# SFPGA.net
KiCad netlist of a schematic drawn in Altium Designer
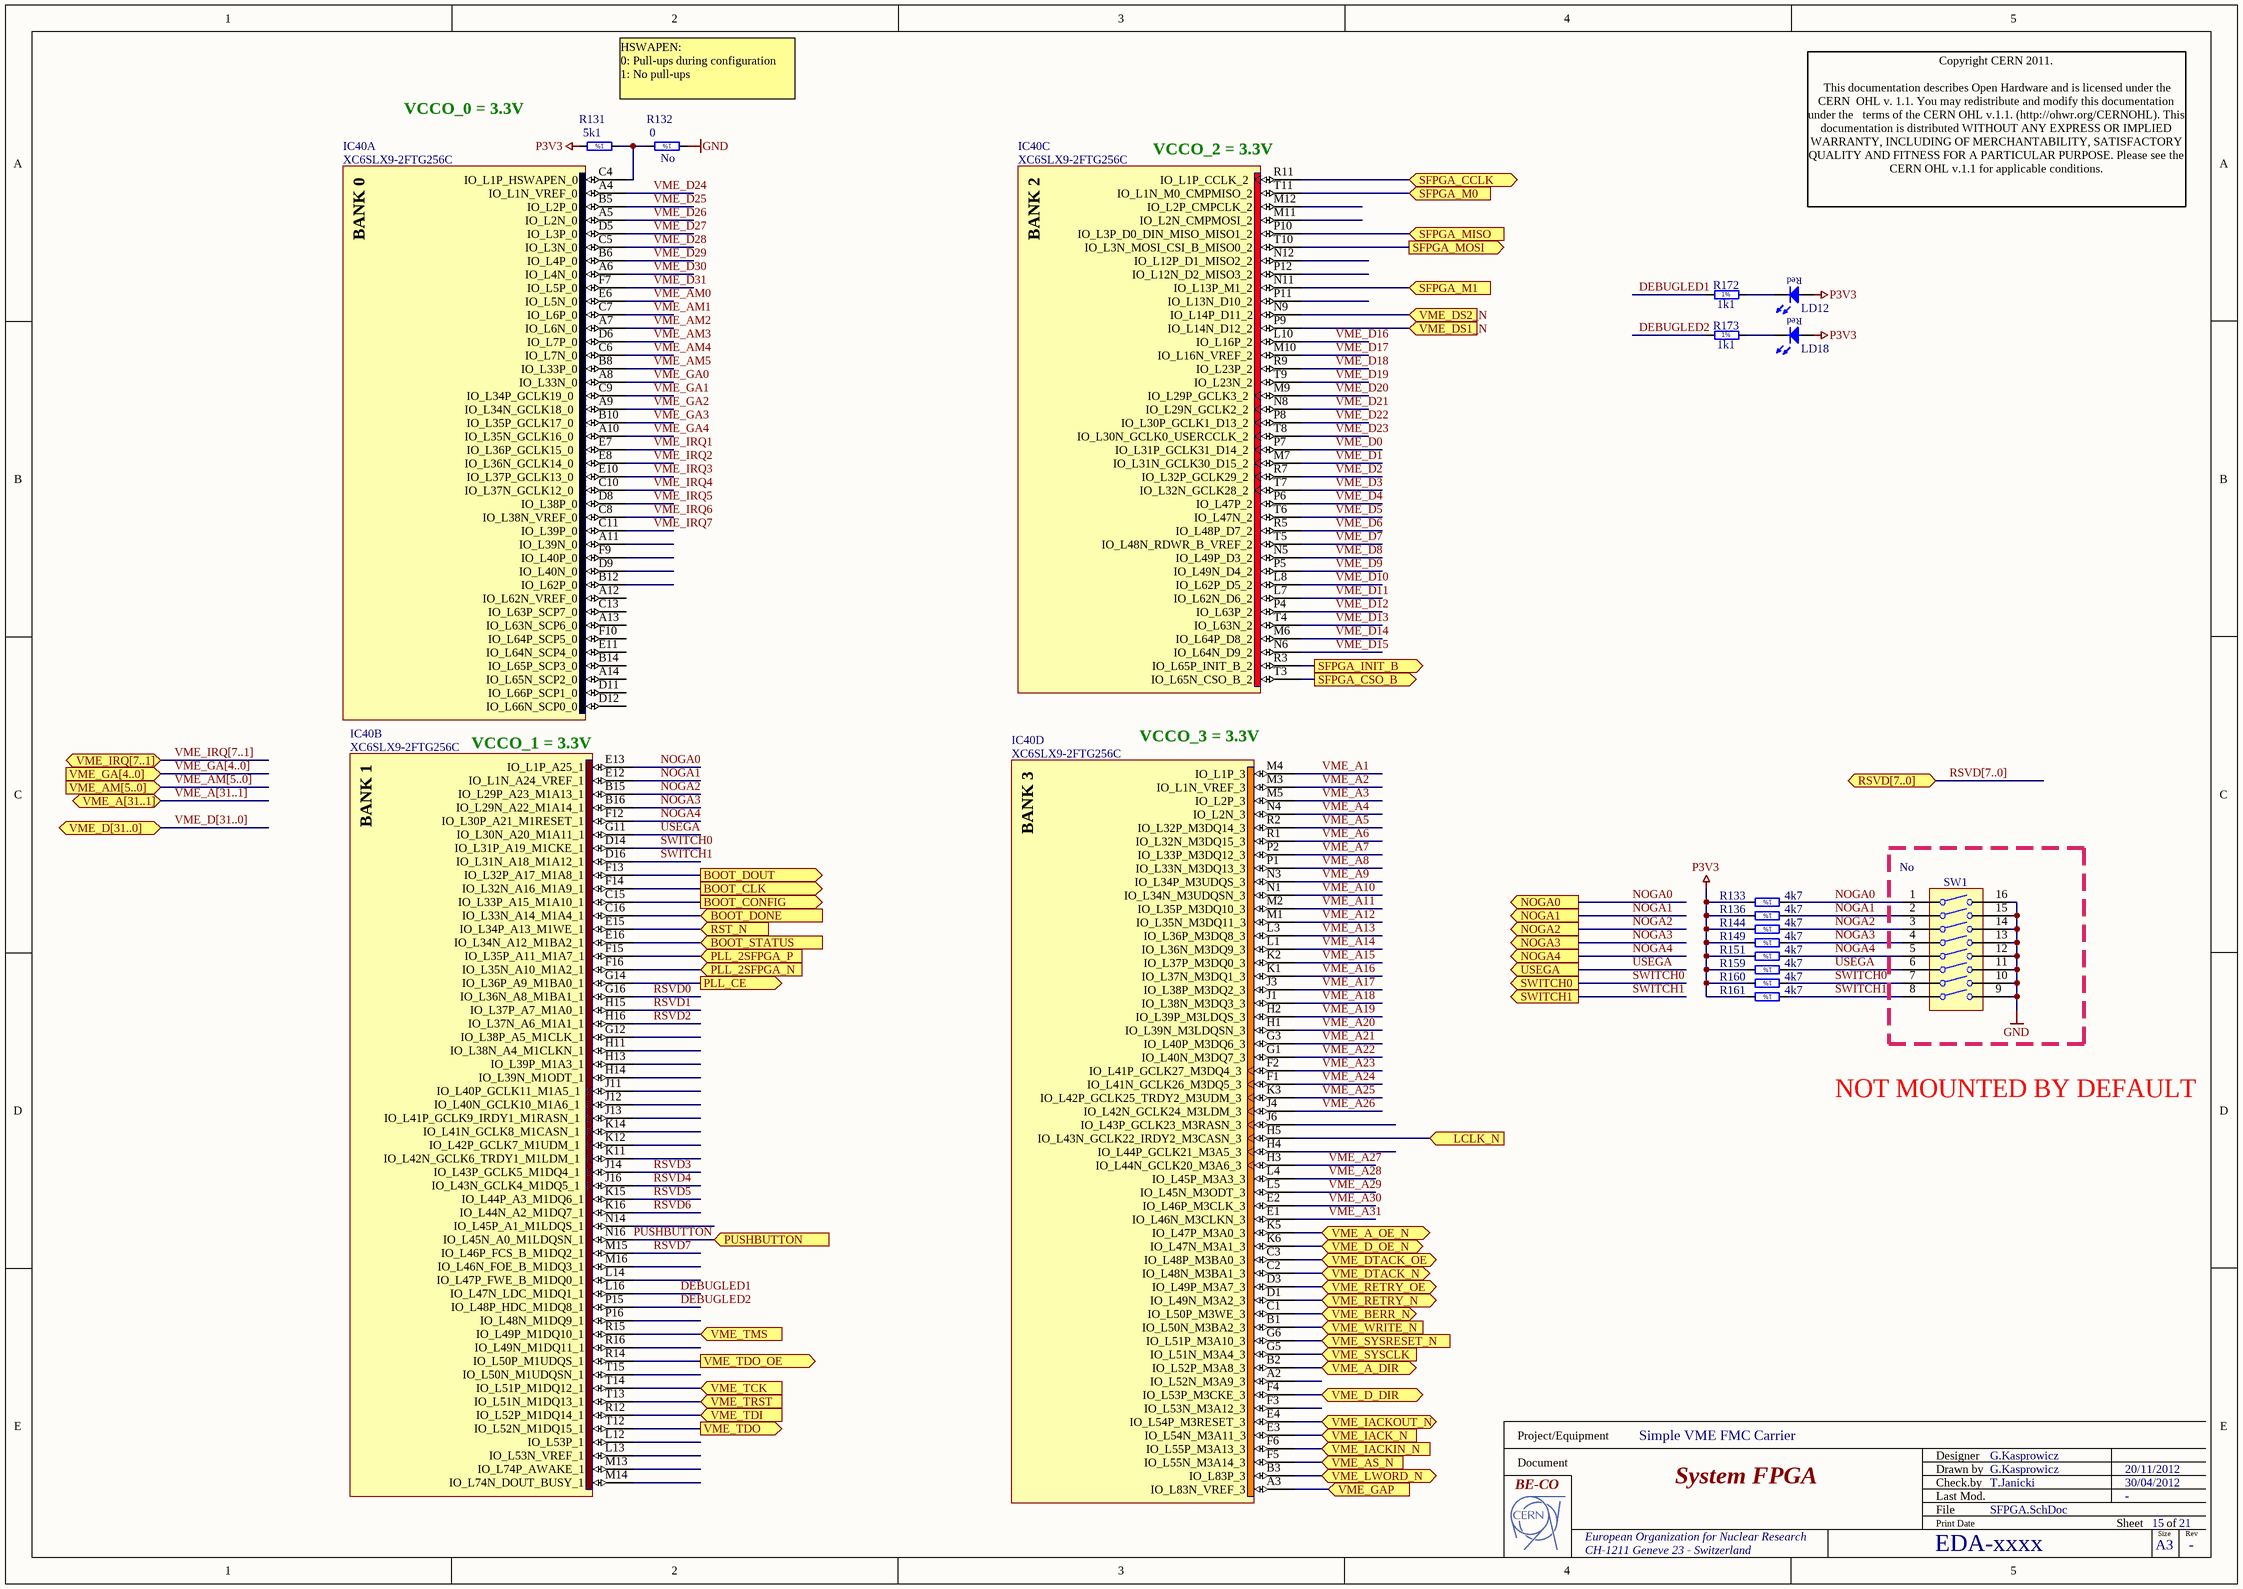
[diagram p0: SFPGA.SchDoc]

(export (version "E")
  (design (tool "Eeschema 10.0.6"))
  (components
    (comp (ref "IC40")
      (value "XC6SLX9-2FTG256C")
      (footprint "BGA256C100P16X16_1700X1700X155")
      (fields (field (name "MANUFACTURER") "XILINX") (field (name "AUTHOR") "CERN DEM JLC"))
      (libsource (lib "ICs And Semiconductors") (part "XC6SLX9-2FTG256C"))
    )
    (comp (ref "LD12")
      (value "Red")
      (footprint "LEDC1608X80N_RED")
      (description "LED Red 1C 2A")
      (fields
        (field (name "PART NUMBER") "LED_ROHM_SML-311UTT86K")
        (field (name "MANUFACTURER") "ROHM")
        (field (name "AUTHOR") "CERN DEM JLC")
      )
      (libsource (lib "ICs And Semiconductors") (part "LED Red 1C 2A"))
    )
    (comp (ref "LD18")
      (value "Red")
      (footprint "LEDC1608X80N_RED")
      (description "LED Red 1C 2A")
      (fields
        (field (name "PART NUMBER") "LED_ROHM_SML-311UTT86K")
        (field (name "MANUFACTURER") "ROHM")
        (field (name "AUTHOR") "CERN DEM JLC")
      )
      (libsource (lib "ICs And Semiconductors") (part "LED Red 1C 2A"))
    )
    (comp (ref "R131")
      (value "5k1")
      (footprint "RESC1608X55N")
      (description "Resistor - 1%")
      (fields
        (field (name "PART NUMBER") "R0603_5K1_1%_0.1W_100PPM")
        (field (name "POWER") "0.1W")
        (field (name "AUTHOR") "CERN DEM JLC")
      )
      (libsource (lib "Resistors") (part "Resistor - 1%"))
    )
    (comp (ref "R132")
      (value "0")
      (footprint "RESC1608X55N")
      (description "Resistor - 1%")
      (fields
        (field (name "PART NUMBER") "R0603_0R_JUMPER")
        (field (name "MANUFACTURER") "GENERIC")
        (field (name "MOUNTED") "No")
        (field (name "AUTHOR") "CERN DEM JLC")
      )
      (libsource (lib "Resistors") (part "Resistor - 1%"))
    )
    (comp (ref "R133")
      (value "4k7")
      (footprint "RESC1608X55N")
      (description "Resistor - 1%")
      (fields
        (field (name "PART NUMBER") "R0603_4K7_1%_0.1W_100PPM")
        (field (name "POWER") "0.1W")
        (field (name "AUTHOR") "CERN DEM JLC")
      )
      (libsource (lib "Resistors") (part "Resistor - 1%"))
    )
    (comp (ref "R136")
      (value "4k7")
      (footprint "RESC1608X55N")
      (description "Resistor - 1%")
      (fields
        (field (name "PART NUMBER") "R0603_4K7_1%_0.1W_100PPM")
        (field (name "POWER") "0.1W")
        (field (name "AUTHOR") "CERN DEM JLC")
      )
      (libsource (lib "Resistors") (part "Resistor - 1%"))
    )
    (comp (ref "R144")
      (value "4k7")
      (footprint "RESC1608X55N")
      (description "Resistor - 1%")
      (fields
        (field (name "PART NUMBER") "R0603_4K7_1%_0.1W_100PPM")
        (field (name "POWER") "0.1W")
        (field (name "AUTHOR") "CERN DEM JLC")
      )
      (libsource (lib "Resistors") (part "Resistor - 1%"))
    )
    (comp (ref "R149")
      (value "4k7")
      (footprint "RESC1608X55N")
      (description "Resistor - 1%")
      (fields
        (field (name "PART NUMBER") "R0603_4K7_1%_0.1W_100PPM")
        (field (name "POWER") "0.1W")
        (field (name "AUTHOR") "CERN DEM JLC")
      )
      (libsource (lib "Resistors") (part "Resistor - 1%"))
    )
    (comp (ref "R151")
      (value "4k7")
      (footprint "RESC1608X55N")
      (description "Resistor - 1%")
      (fields
        (field (name "PART NUMBER") "R0603_4K7_1%_0.1W_100PPM")
        (field (name "POWER") "0.1W")
        (field (name "AUTHOR") "CERN DEM JLC")
      )
      (libsource (lib "Resistors") (part "Resistor - 1%"))
    )
    (comp (ref "R159")
      (value "4k7")
      (footprint "RESC1608X55N")
      (description "Resistor - 1%")
      (fields
        (field (name "PART NUMBER") "R0603_4K7_1%_0.1W_100PPM")
        (field (name "POWER") "0.1W")
        (field (name "AUTHOR") "CERN DEM JLC")
      )
      (libsource (lib "Resistors") (part "Resistor - 1%"))
    )
    (comp (ref "R160")
      (value "4k7")
      (footprint "RESC1608X55N")
      (description "Resistor - 1%")
      (fields
        (field (name "PART NUMBER") "R0603_4K7_1%_0.1W_100PPM")
        (field (name "POWER") "0.1W")
        (field (name "AUTHOR") "CERN DEM JLC")
      )
      (libsource (lib "Resistors") (part "Resistor - 1%"))
    )
    (comp (ref "R161")
      (value "4k7")
      (footprint "RESC1608X55N")
      (description "Resistor - 1%")
      (fields
        (field (name "PART NUMBER") "R0603_4K7_1%_0.1W_100PPM")
        (field (name "POWER") "0.1W")
        (field (name "AUTHOR") "CERN DEM JLC")
      )
      (libsource (lib "Resistors") (part "Resistor - 1%"))
    )
    (comp (ref "R172")
      (value "1k1")
      (footprint "RESC1608X55N")
      (description "Resistor - 1%")
      (fields
        (field (name "PART NUMBER") "R0603_1K1_1%_0.1W_100PPM")
        (field (name "POWER") "0.1W")
        (field (name "AUTHOR") "CERN DEM JLC")
      )
      (libsource (lib "Resistors") (part "Resistor - 1%"))
    )
    (comp (ref "R173")
      (value "1k1")
      (footprint "RESC1608X55N")
      (description "Resistor - 1%")
      (fields
        (field (name "PART NUMBER") "R0603_1K1_1%_0.1W_100PPM")
        (field (name "POWER") "0.1W")
        (field (name "AUTHOR") "CERN DEM JLC")
      )
      (libsource (lib "Resistors") (part "Resistor - 1%"))
    )
    (comp (ref "SW1")
      (value "Switch")
      (footprint "SW_TYCO_1-1571983-0")
      (description "8 Ways SPST DIP Switch")
      (fields
        (field (name "PART NUMBER") "SW_TYCO_1-1571983-0")
        (field (name "MOUNTED") "No")
        (field (name "MANUFACTURER") "TYCO")
        (field (name "AUTHOR") "CERN DEM JLC")
      )
      (libsource (lib "Eletro-mechanical") (part "SW 8x SPST DIP Switch"))
    )
  )
  (nets
    (net (code "1") (name "/BOOT_CLK") (class "Default")
      (node (ref "IC40") (pin "F14") (pinfunction "IO_L32N_A16_M1A9_1_F14") (pintype "bidirectional"))
    )
    (net (code "2") (name "/BOOT_CONFIG") (class "Default")
      (node (ref "IC40") (pin "C15") (pinfunction "IO_L33P_A15_M1A10_1_C15") (pintype "bidirectional"))
    )
    (net (code "3") (name "/BOOT_DONE") (class "Default")
      (node (ref "IC40") (pin "C16") (pinfunction "IO_L33N_A14_M1A4_1_C16") (pintype "bidirectional"))
    )
    (net (code "4") (name "/BOOT_DOUT") (class "Default")
      (node (ref "IC40") (pin "F13") (pinfunction "IO_L32P_A17_M1A8_1_F13") (pintype "bidirectional"))
    )
    (net (code "5") (name "/BOOT_STATUS") (class "Default")
      (node (ref "IC40") (pin "E16") (pinfunction "IO_L34N_A12_M1BA2_1_E16") (pintype "bidirectional"))
    )
    (net (code "6") (name "/DEBUGLED1") (class "Default")
      (node (ref "IC40") (pin "L16") (pinfunction "IO_L47N_LDC_M1DQ1_1_L16") (pintype "bidirectional"))
      (node (ref "R172") (pin "1") (pinfunction "1_1") (pintype "passive"))
    )
    (net (code "7") (name "/DEBUGLED2") (class "Default")
      (node (ref "IC40") (pin "P15") (pinfunction "IO_L48P_HDC_M1DQ8_1_P15") (pintype "bidirectional"))
      (node (ref "R173") (pin "1") (pinfunction "1_1") (pintype "passive"))
    )
    (net (code "8") (name "/LCLK_N") (class "Default")
      (node (ref "IC40") (pin "H5") (pinfunction "IO_L43N_GCLK22_IRDY2_M3CASN_3_H5") (pintype "bidirectional"))
    )
    (net (code "9") (name "/NOGA0") (class "Default")
      (node (ref "IC40") (pin "E13") (pinfunction "IO_L1P_A25_1_E13") (pintype "bidirectional"))
      (node (ref "R133") (pin "1") (pinfunction "1_1") (pintype "passive"))
      (node (ref "SW1") (pin "1") (pinfunction "1_1") (pintype "passive"))
    )
    (net (code "10") (name "/NOGA1") (class "Default")
      (node (ref "IC40") (pin "E12") (pinfunction "IO_L1N_A24_VREF_1_E12") (pintype "bidirectional"))
      (node (ref "R136") (pin "1") (pinfunction "1_1") (pintype "passive"))
      (node (ref "SW1") (pin "2") (pinfunction "2_2") (pintype "passive"))
    )
    (net (code "11") (name "/NOGA2") (class "Default")
      (node (ref "IC40") (pin "B15") (pinfunction "IO_L29P_A23_M1A13_1_B15") (pintype "bidirectional"))
      (node (ref "R144") (pin "1") (pinfunction "1_1") (pintype "passive"))
      (node (ref "SW1") (pin "3") (pinfunction "3_3") (pintype "passive"))
    )
    (net (code "12") (name "/NOGA3") (class "Default")
      (node (ref "IC40") (pin "B16") (pinfunction "IO_L29N_A22_M1A14_1_B16") (pintype "bidirectional"))
      (node (ref "R149") (pin "1") (pinfunction "1_1") (pintype "passive"))
      (node (ref "SW1") (pin "4") (pinfunction "4_4") (pintype "passive"))
    )
    (net (code "13") (name "/NOGA4") (class "Default")
      (node (ref "IC40") (pin "F12") (pinfunction "IO_L30P_A21_M1RESET_1_F12") (pintype "bidirectional"))
      (node (ref "R151") (pin "1") (pinfunction "1_1") (pintype "passive"))
      (node (ref "SW1") (pin "5") (pinfunction "5_5") (pintype "passive"))
    )
    (net (code "14") (name "/PLL_2SFPGA_N") (class "Default")
      (node (ref "IC40") (pin "F16") (pinfunction "IO_L35N_A10_M1A2_1_F16") (pintype "bidirectional"))
    )
    (net (code "15") (name "/PLL_2SFPGA_P") (class "Default")
      (node (ref "IC40") (pin "F15") (pinfunction "IO_L35P_A11_M1A7_1_F15") (pintype "bidirectional"))
    )
    (net (code "16") (name "/PLL_CE") (class "Default")
      (node (ref "IC40") (pin "G14") (pinfunction "IO_L36P_A9_M1BA0_1_G14") (pintype "bidirectional"))
    )
    (net (code "17") (name "/PUSHBUTTON") (class "Default")
      (node (ref "IC40") (pin "N16") (pinfunction "IO_L45N_A0_M1LDQSN_1_N16") (pintype "bidirectional"))
    )
    (net (code "18") (name "/RST_N") (class "Default")
      (node (ref "IC40") (pin "E15") (pinfunction "IO_L34P_A13_M1WE_1_E15") (pintype "bidirectional"))
    )
    (net (code "19") (name "/RSVD0") (class "Default")
      (node (ref "IC40") (pin "G16") (pinfunction "IO_L36N_A8_M1BA1_1_G16") (pintype "bidirectional"))
    )
    (net (code "20") (name "/RSVD1") (class "Default")
      (node (ref "IC40") (pin "H15") (pinfunction "IO_L37P_A7_M1A0_1_H15") (pintype "bidirectional"))
    )
    (net (code "21") (name "/RSVD2") (class "Default")
      (node (ref "IC40") (pin "H16") (pinfunction "IO_L37N_A6_M1A1_1_H16") (pintype "bidirectional"))
    )
    (net (code "22") (name "/RSVD3") (class "Default")
      (node (ref "IC40") (pin "J14") (pinfunction "IO_L43P_GCLK5_M1DQ4_1_J14") (pintype "bidirectional"))
    )
    (net (code "23") (name "/RSVD4") (class "Default")
      (node (ref "IC40") (pin "J16") (pinfunction "IO_L43N_GCLK4_M1DQ5_1_J16") (pintype "bidirectional"))
    )
    (net (code "24") (name "/RSVD5") (class "Default")
      (node (ref "IC40") (pin "K15") (pinfunction "IO_L44P_A3_M1DQ6_1_K15") (pintype "bidirectional"))
    )
    (net (code "25") (name "/RSVD6") (class "Default")
      (node (ref "IC40") (pin "K16") (pinfunction "IO_L44N_A2_M1DQ7_1_K16") (pintype "bidirectional"))
    )
    (net (code "26") (name "/RSVD7") (class "Default")
      (node (ref "IC40") (pin "M15") (pinfunction "IO_L46P_FCS_B_M1DQ2_1_M15") (pintype "bidirectional"))
    )
    (net (code "28") (name "/SFPGA_CCLK") (class "Default")
      (node (ref "IC40") (pin "R11") (pinfunction "IO_L1P_CCLK_2_R11") (pintype "bidirectional"))
    )
    (net (code "29") (name "/SFPGA_CSO_B") (class "Default")
      (node (ref "IC40") (pin "T3") (pinfunction "IO_L65N_CSO_B_2_T3") (pintype "bidirectional"))
    )
    (net (code "30") (name "/SFPGA_INIT_B") (class "Default")
      (node (ref "IC40") (pin "R3") (pinfunction "IO_L65P_INIT_B_2_R3") (pintype "bidirectional"))
    )
    (net (code "31") (name "/SFPGA_M0") (class "Default")
      (node (ref "IC40") (pin "T11") (pinfunction "IO_L1N_M0_CMPMISO_2_T11") (pintype "bidirectional"))
    )
    (net (code "32") (name "/SFPGA_M1") (class "Default")
      (node (ref "IC40") (pin "N11") (pinfunction "IO_L13P_M1_2_N11") (pintype "bidirectional"))
    )
    (net (code "33") (name "/SFPGA_MISO") (class "Default")
      (node (ref "IC40") (pin "P10") (pinfunction "IO_L3P_D0_DIN_MISO_MISO1_2_P10") (pintype "bidirectional"))
    )
    (net (code "34") (name "/SFPGA_MOSI") (class "Default")
      (node (ref "IC40") (pin "T10") (pinfunction "IO_L3N_MOSI_CSI_B_MISO0_2_T10") (pintype "bidirectional"))
    )
    (net (code "35") (name "/SWITCH0") (class "Default")
      (node (ref "IC40") (pin "D14") (pinfunction "IO_L31P_A19_M1CKE_1_D14") (pintype "bidirectional"))
      (node (ref "R160") (pin "1") (pinfunction "1_1") (pintype "passive"))
      (node (ref "SW1") (pin "7") (pinfunction "7_7") (pintype "passive"))
    )
    (net (code "36") (name "/SWITCH1") (class "Default")
      (node (ref "IC40") (pin "D16") (pinfunction "IO_L31N_A18_M1A12_1_D16") (pintype "bidirectional"))
      (node (ref "R161") (pin "1") (pinfunction "1_1") (pintype "passive"))
      (node (ref "SW1") (pin "8") (pinfunction "8_8") (pintype "passive"))
    )
    (net (code "37") (name "/USEGA") (class "Default")
      (node (ref "IC40") (pin "G11") (pinfunction "IO_L30N_A20_M1A11_1_G11") (pintype "bidirectional"))
      (node (ref "R159") (pin "1") (pinfunction "1_1") (pintype "passive"))
      (node (ref "SW1") (pin "6") (pinfunction "6_6") (pintype "passive"))
    )
    (net (code "38") (name "/VME_A1") (class "Default")
      (node (ref "IC40") (pin "M4") (pinfunction "IO_L1P_3_M4") (pintype "bidirectional"))
    )
    (net (code "39") (name "/VME_A2") (class "Default")
      (node (ref "IC40") (pin "M3") (pinfunction "IO_L1N_VREF_3_M3") (pintype "bidirectional"))
    )
    (net (code "40") (name "/VME_A3") (class "Default")
      (node (ref "IC40") (pin "M5") (pinfunction "IO_L2P_3_M5") (pintype "bidirectional"))
    )
    (net (code "41") (name "/VME_A4") (class "Default")
      (node (ref "IC40") (pin "N4") (pinfunction "IO_L2N_3_N4") (pintype "bidirectional"))
    )
    (net (code "42") (name "/VME_A5") (class "Default")
      (node (ref "IC40") (pin "R2") (pinfunction "IO_L32P_M3DQ14_3_R2") (pintype "bidirectional"))
    )
    (net (code "43") (name "/VME_A6") (class "Default")
      (node (ref "IC40") (pin "R1") (pinfunction "IO_L32N_M3DQ15_3_R1") (pintype "bidirectional"))
    )
    (net (code "44") (name "/VME_A7") (class "Default")
      (node (ref "IC40") (pin "P2") (pinfunction "IO_L33P_M3DQ12_3_P2") (pintype "bidirectional"))
    )
    (net (code "45") (name "/VME_A8") (class "Default")
      (node (ref "IC40") (pin "P1") (pinfunction "IO_L33N_M3DQ13_3_P1") (pintype "bidirectional"))
    )
    (net (code "46") (name "/VME_A9") (class "Default")
      (node (ref "IC40") (pin "N3") (pinfunction "IO_L34P_M3UDQS_3_N3") (pintype "bidirectional"))
    )
    (net (code "47") (name "/VME_A10") (class "Default")
      (node (ref "IC40") (pin "N1") (pinfunction "IO_L34N_M3UDQSN_3_N1") (pintype "bidirectional"))
    )
    (net (code "48") (name "/VME_A11") (class "Default")
      (node (ref "IC40") (pin "M2") (pinfunction "IO_L35P_M3DQ10_3_M2") (pintype "bidirectional"))
    )
    (net (code "49") (name "/VME_A12") (class "Default")
      (node (ref "IC40") (pin "M1") (pinfunction "IO_L35N_M3DQ11_3_M1") (pintype "bidirectional"))
    )
    (net (code "50") (name "/VME_A13") (class "Default")
      (node (ref "IC40") (pin "L3") (pinfunction "IO_L36P_M3DQ8_3_L3") (pintype "bidirectional"))
    )
    (net (code "51") (name "/VME_A14") (class "Default")
      (node (ref "IC40") (pin "L1") (pinfunction "IO_L36N_M3DQ9_3_L1") (pintype "bidirectional"))
    )
    (net (code "52") (name "/VME_A15") (class "Default")
      (node (ref "IC40") (pin "K2") (pinfunction "IO_L37P_M3DQ0_3_K2") (pintype "bidirectional"))
    )
    (net (code "53") (name "/VME_A16") (class "Default")
      (node (ref "IC40") (pin "K1") (pinfunction "IO_L37N_M3DQ1_3_K1") (pintype "bidirectional"))
    )
    (net (code "54") (name "/VME_A17") (class "Default")
      (node (ref "IC40") (pin "J3") (pinfunction "IO_L38P_M3DQ2_3_J3") (pintype "bidirectional"))
    )
    (net (code "55") (name "/VME_A18") (class "Default")
      (node (ref "IC40") (pin "J1") (pinfunction "IO_L38N_M3DQ3_3_J1") (pintype "bidirectional"))
    )
    (net (code "56") (name "/VME_A19") (class "Default")
      (node (ref "IC40") (pin "H2") (pinfunction "IO_L39P_M3LDQS_3_H2") (pintype "bidirectional"))
    )
    (net (code "57") (name "/VME_A20") (class "Default")
      (node (ref "IC40") (pin "H1") (pinfunction "IO_L39N_M3LDQSN_3_H1") (pintype "bidirectional"))
    )
    (net (code "58") (name "/VME_A21") (class "Default")
      (node (ref "IC40") (pin "G3") (pinfunction "IO_L40P_M3DQ6_3_G3") (pintype "bidirectional"))
    )
    (net (code "59") (name "/VME_A22") (class "Default")
      (node (ref "IC40") (pin "G1") (pinfunction "IO_L40N_M3DQ7_3_G1") (pintype "bidirectional"))
    )
    (net (code "60") (name "/VME_A23") (class "Default")
      (node (ref "IC40") (pin "F2") (pinfunction "IO_L41P_GCLK27_M3DQ4_3_F2") (pintype "bidirectional"))
    )
    (net (code "61") (name "/VME_A24") (class "Default")
      (node (ref "IC40") (pin "F1") (pinfunction "IO_L41N_GCLK26_M3DQ5_3_F1") (pintype "bidirectional"))
    )
    (net (code "62") (name "/VME_A25") (class "Default")
      (node (ref "IC40") (pin "K3") (pinfunction "IO_L42P_GCLK25_TRDY2_M3UDM_3_K3") (pintype "bidirectional"))
    )
    (net (code "63") (name "/VME_A26") (class "Default")
      (node (ref "IC40") (pin "J4") (pinfunction "IO_L42N_GCLK24_M3LDM_3_J4") (pintype "bidirectional"))
    )
    (net (code "64") (name "/VME_A27") (class "Default")
      (node (ref "IC40") (pin "H3") (pinfunction "IO_L44N_GCLK20_M3A6_3_H3") (pintype "bidirectional"))
    )
    (net (code "65") (name "/VME_A28") (class "Default")
      (node (ref "IC40") (pin "L4") (pinfunction "IO_L45P_M3A3_3_L4") (pintype "bidirectional"))
    )
    (net (code "66") (name "/VME_A29") (class "Default")
      (node (ref "IC40") (pin "L5") (pinfunction "IO_L45N_M3ODT_3_L5") (pintype "bidirectional"))
    )
    (net (code "67") (name "/VME_A30") (class "Default")
      (node (ref "IC40") (pin "E2") (pinfunction "IO_L46P_M3CLK_3_E2") (pintype "bidirectional"))
    )
    (net (code "68") (name "/VME_A31") (class "Default")
      (node (ref "IC40") (pin "E1") (pinfunction "IO_L46N_M3CLKN_3_E1") (pintype "bidirectional"))
    )
    (net (code "69") (name "/VME_AM0") (class "Default")
      (node (ref "IC40") (pin "E6") (pinfunction "IO_L5N_0_E6") (pintype "bidirectional"))
    )
    (net (code "70") (name "/VME_AM1") (class "Default")
      (node (ref "IC40") (pin "C7") (pinfunction "IO_L6P_0_C7") (pintype "bidirectional"))
    )
    (net (code "71") (name "/VME_AM2") (class "Default")
      (node (ref "IC40") (pin "A7") (pinfunction "IO_L6N_0_A7") (pintype "bidirectional"))
    )
    (net (code "72") (name "/VME_AM3") (class "Default")
      (node (ref "IC40") (pin "D6") (pinfunction "IO_L7P_0_D6") (pintype "bidirectional"))
    )
    (net (code "73") (name "/VME_AM4") (class "Default")
      (node (ref "IC40") (pin "C6") (pinfunction "IO_L7N_0_C6") (pintype "bidirectional"))
    )
    (net (code "74") (name "/VME_AM5") (class "Default")
      (node (ref "IC40") (pin "B8") (pinfunction "IO_L33P_0_B8") (pintype "bidirectional"))
    )
    (net (code "76") (name "/VME_AS_N") (class "Default")
      (node (ref "IC40") (pin "F5") (pinfunction "IO_L55N_M3A14_3_F5") (pintype "bidirectional"))
    )
    (net (code "78") (name "/VME_A_DIR") (class "Default")
      (node (ref "IC40") (pin "B2") (pinfunction "IO_L52P_M3A8_3_B2") (pintype "bidirectional"))
    )
    (net (code "79") (name "/VME_A_OE_N") (class "Default")
      (node (ref "IC40") (pin "K5") (pinfunction "IO_L47P_M3A0_3_K5") (pintype "bidirectional"))
    )
    (net (code "80") (name "/VME_BERR_N") (class "Default")
      (node (ref "IC40") (pin "C1") (pinfunction "IO_L50P_M3WE_3_C1") (pintype "bidirectional"))
    )
    (net (code "81") (name "/VME_D0") (class "Default")
      (node (ref "IC40") (pin "P7") (pinfunction "IO_L31P_GCLK31_D14_2_P7") (pintype "bidirectional"))
    )
    (net (code "82") (name "/VME_D1") (class "Default")
      (node (ref "IC40") (pin "M7") (pinfunction "IO_L31N_GCLK30_D15_2_M7") (pintype "bidirectional"))
    )
    (net (code "83") (name "/VME_D2") (class "Default")
      (node (ref "IC40") (pin "R7") (pinfunction "IO_L32P_GCLK29_2_R7") (pintype "bidirectional"))
    )
    (net (code "84") (name "/VME_D3") (class "Default")
      (node (ref "IC40") (pin "T7") (pinfunction "IO_L32N_GCLK28_2_T7") (pintype "bidirectional"))
    )
    (net (code "85") (name "/VME_D4") (class "Default")
      (node (ref "IC40") (pin "P6") (pinfunction "IO_L47P_2_P6") (pintype "bidirectional"))
    )
    (net (code "86") (name "/VME_D5") (class "Default")
      (node (ref "IC40") (pin "T6") (pinfunction "IO_L47N_2_T6") (pintype "bidirectional"))
    )
    (net (code "87") (name "/VME_D6") (class "Default")
      (node (ref "IC40") (pin "R5") (pinfunction "IO_L48P_D7_2_R5") (pintype "bidirectional"))
    )
    (net (code "88") (name "/VME_D7") (class "Default")
      (node (ref "IC40") (pin "T5") (pinfunction "IO_L48N_RDWR_B_VREF_2_T5") (pintype "bidirectional"))
    )
    (net (code "89") (name "/VME_D8") (class "Default")
      (node (ref "IC40") (pin "N5") (pinfunction "IO_L49P_D3_2_N5") (pintype "bidirectional"))
    )
    (net (code "90") (name "/VME_D9") (class "Default")
      (node (ref "IC40") (pin "P5") (pinfunction "IO_L49N_D4_2_P5") (pintype "bidirectional"))
    )
    (net (code "91") (name "/VME_D10") (class "Default")
      (node (ref "IC40") (pin "L8") (pinfunction "IO_L62P_D5_2_L8") (pintype "bidirectional"))
    )
    (net (code "92") (name "/VME_D11") (class "Default")
      (node (ref "IC40") (pin "L7") (pinfunction "IO_L62N_D6_2_L7") (pintype "bidirectional"))
    )
    (net (code "93") (name "/VME_D12") (class "Default")
      (node (ref "IC40") (pin "P4") (pinfunction "IO_L63P_2_P4") (pintype "bidirectional"))
    )
    (net (code "94") (name "/VME_D13") (class "Default")
      (node (ref "IC40") (pin "T4") (pinfunction "IO_L63N_2_T4") (pintype "bidirectional"))
    )
    (net (code "95") (name "/VME_D14") (class "Default")
      (node (ref "IC40") (pin "M6") (pinfunction "IO_L64P_D8_2_M6") (pintype "bidirectional"))
    )
    (net (code "96") (name "/VME_D15") (class "Default")
      (node (ref "IC40") (pin "N6") (pinfunction "IO_L64N_D9_2_N6") (pintype "bidirectional"))
    )
    (net (code "97") (name "/VME_D16") (class "Default")
      (node (ref "IC40") (pin "L10") (pinfunction "IO_L16P_2_L10") (pintype "bidirectional"))
    )
    (net (code "98") (name "/VME_D17") (class "Default")
      (node (ref "IC40") (pin "M10") (pinfunction "IO_L16N_VREF_2_M10") (pintype "bidirectional"))
    )
    (net (code "99") (name "/VME_D18") (class "Default")
      (node (ref "IC40") (pin "R9") (pinfunction "IO_L23P_2_R9") (pintype "bidirectional"))
    )
    (net (code "100") (name "/VME_D19") (class "Default")
      (node (ref "IC40") (pin "T9") (pinfunction "IO_L23N_2_T9") (pintype "bidirectional"))
    )
    (net (code "101") (name "/VME_D20") (class "Default")
      (node (ref "IC40") (pin "M9") (pinfunction "IO_L29P_GCLK3_2_M9") (pintype "bidirectional"))
    )
    (net (code "102") (name "/VME_D21") (class "Default")
      (node (ref "IC40") (pin "N8") (pinfunction "IO_L29N_GCLK2_2_N8") (pintype "bidirectional"))
    )
    (net (code "103") (name "/VME_D22") (class "Default")
      (node (ref "IC40") (pin "P8") (pinfunction "IO_L30P_GCLK1_D13_2_P8") (pintype "bidirectional"))
    )
    (net (code "104") (name "/VME_D23") (class "Default")
      (node (ref "IC40") (pin "T8") (pinfunction "IO_L30N_GCLK0_USERCCLK_2_T8") (pintype "bidirectional"))
    )
    (net (code "105") (name "/VME_D24") (class "Default")
      (node (ref "IC40") (pin "A4") (pinfunction "IO_L1N_VREF_0_A4") (pintype "bidirectional"))
    )
    (net (code "106") (name "/VME_D25") (class "Default")
      (node (ref "IC40") (pin "B5") (pinfunction "IO_L2P_0_B5") (pintype "bidirectional"))
    )
    (net (code "107") (name "/VME_D26") (class "Default")
      (node (ref "IC40") (pin "A5") (pinfunction "IO_L2N_0_A5") (pintype "bidirectional"))
    )
    (net (code "108") (name "/VME_D27") (class "Default")
      (node (ref "IC40") (pin "D5") (pinfunction "IO_L3P_0_D5") (pintype "bidirectional"))
    )
    (net (code "109") (name "/VME_D28") (class "Default")
      (node (ref "IC40") (pin "C5") (pinfunction "IO_L3N_0_C5") (pintype "bidirectional"))
    )
    (net (code "110") (name "/VME_D29") (class "Default")
      (node (ref "IC40") (pin "B6") (pinfunction "IO_L4P_0_B6") (pintype "bidirectional"))
    )
    (net (code "111") (name "/VME_D30") (class "Default")
      (node (ref "IC40") (pin "A6") (pinfunction "IO_L4N_0_A6") (pintype "bidirectional"))
    )
    (net (code "112") (name "/VME_D31") (class "Default")
      (node (ref "IC40") (pin "F7") (pinfunction "IO_L5P_0_F7") (pintype "bidirectional"))
    )
    (net (code "113") (name "/VME_DS1_N") (class "Default")
      (node (ref "IC40") (pin "P9") (pinfunction "IO_L14N_D12_2_P9") (pintype "bidirectional"))
    )
    (net (code "114") (name "/VME_DS2_N") (class "Default")
      (node (ref "IC40") (pin "N9") (pinfunction "IO_L14P_D11_2_N9") (pintype "bidirectional"))
    )
    (net (code "115") (name "/VME_DTACK_N") (class "Default")
      (node (ref "IC40") (pin "C2") (pinfunction "IO_L48N_M3BA1_3_C2") (pintype "bidirectional"))
    )
    (net (code "116") (name "/VME_DTACK_OE") (class "Default")
      (node (ref "IC40") (pin "C3") (pinfunction "IO_L48P_M3BA0_3_C3") (pintype "bidirectional"))
    )
    (net (code "118") (name "/VME_D_DIR") (class "Default")
      (node (ref "IC40") (pin "F4") (pinfunction "IO_L53P_M3CKE_3_F4") (pintype "bidirectional"))
    )
    (net (code "119") (name "/VME_D_OE_N") (class "Default")
      (node (ref "IC40") (pin "K6") (pinfunction "IO_L47N_M3A1_3_K6") (pintype "bidirectional"))
    )
    (net (code "120") (name "/VME_GA0") (class "Default")
      (node (ref "IC40") (pin "A8") (pinfunction "IO_L33N_0_A8") (pintype "bidirectional"))
    )
    (net (code "121") (name "/VME_GA1") (class "Default")
      (node (ref "IC40") (pin "C9") (pinfunction "IO_L34P_GCLK19_0_C9") (pintype "bidirectional"))
    )
    (net (code "122") (name "/VME_GA2") (class "Default")
      (node (ref "IC40") (pin "A9") (pinfunction "IO_L34N_GCLK18_0_A9") (pintype "bidirectional"))
    )
    (net (code "123") (name "/VME_GA3") (class "Default")
      (node (ref "IC40") (pin "B10") (pinfunction "IO_L35P_GCLK17_0_B10") (pintype "bidirectional"))
    )
    (net (code "124") (name "/VME_GA4") (class "Default")
      (node (ref "IC40") (pin "A10") (pinfunction "IO_L35N_GCLK16_0_A10") (pintype "bidirectional"))
    )
    (net (code "125") (name "/VME_GAP") (class "Default")
      (node (ref "IC40") (pin "A3") (pinfunction "IO_L83N_VREF_3_A3") (pintype "bidirectional"))
    )
    (net (code "127") (name "/VME_IACKIN_N") (class "Default")
      (node (ref "IC40") (pin "F6") (pinfunction "IO_L55P_M3A13_3_F6") (pintype "bidirectional"))
    )
    (net (code "128") (name "/VME_IACKOUT_N") (class "Default")
      (node (ref "IC40") (pin "E4") (pinfunction "IO_L54P_M3RESET_3_E4") (pintype "bidirectional"))
    )
    (net (code "129") (name "/VME_IACK_N") (class "Default")
      (node (ref "IC40") (pin "E3") (pinfunction "IO_L54N_M3A11_3_E3") (pintype "bidirectional"))
    )
    (net (code "130") (name "/VME_IRQ1") (class "Default")
      (node (ref "IC40") (pin "E7") (pinfunction "IO_L36P_GCLK15_0_E7") (pintype "bidirectional"))
    )
    (net (code "131") (name "/VME_IRQ2") (class "Default")
      (node (ref "IC40") (pin "E8") (pinfunction "IO_L36N_GCLK14_0_E8") (pintype "bidirectional"))
    )
    (net (code "132") (name "/VME_IRQ3") (class "Default")
      (node (ref "IC40") (pin "E10") (pinfunction "IO_L37P_GCLK13_0_E10") (pintype "bidirectional"))
    )
    (net (code "133") (name "/VME_IRQ4") (class "Default")
      (node (ref "IC40") (pin "C10") (pinfunction "IO_L37N_GCLK12_0_C10") (pintype "bidirectional"))
    )
    (net (code "134") (name "/VME_IRQ5") (class "Default")
      (node (ref "IC40") (pin "D8") (pinfunction "IO_L38P_0_D8") (pintype "bidirectional"))
    )
    (net (code "135") (name "/VME_IRQ6") (class "Default")
      (node (ref "IC40") (pin "C8") (pinfunction "IO_L38N_VREF_0_C8") (pintype "bidirectional"))
    )
    (net (code "136") (name "/VME_IRQ7") (class "Default")
      (node (ref "IC40") (pin "C11") (pinfunction "IO_L39P_0_C11") (pintype "bidirectional"))
    )
    (net (code "138") (name "/VME_LWORD_N") (class "Default")
      (node (ref "IC40") (pin "B3") (pinfunction "IO_L83P_3_B3") (pintype "bidirectional"))
    )
    (net (code "139") (name "/VME_RETRY_N") (class "Default")
      (node (ref "IC40") (pin "D1") (pinfunction "IO_L49N_M3A2_3_D1") (pintype "bidirectional"))
    )
    (net (code "140") (name "/VME_RETRY_OE") (class "Default")
      (node (ref "IC40") (pin "D3") (pinfunction "IO_L49P_M3A7_3_D3") (pintype "bidirectional"))
    )
    (net (code "141") (name "/VME_SYSCLK") (class "Default")
      (node (ref "IC40") (pin "G5") (pinfunction "IO_L51N_M3A4_3_G5") (pintype "bidirectional"))
    )
    (net (code "142") (name "/VME_SYSRESET_N") (class "Default")
      (node (ref "IC40") (pin "G6") (pinfunction "IO_L51P_M3A10_3_G6") (pintype "bidirectional"))
    )
    (net (code "143") (name "/VME_TCK") (class "Default")
      (node (ref "IC40") (pin "T14") (pinfunction "IO_L51P_M1DQ12_1_T14") (pintype "bidirectional"))
    )
    (net (code "144") (name "/VME_TDI") (class "Default")
      (node (ref "IC40") (pin "R12") (pinfunction "IO_L52P_M1DQ14_1_R12") (pintype "bidirectional"))
    )
    (net (code "145") (name "/VME_TDO") (class "Default")
      (node (ref "IC40") (pin "T12") (pinfunction "IO_L52N_M1DQ15_1_T12") (pintype "bidirectional"))
    )
    (net (code "146") (name "/VME_TDO_OE") (class "Default")
      (node (ref "IC40") (pin "R14") (pinfunction "IO_L50P_M1UDQS_1_R14") (pintype "bidirectional"))
    )
    (net (code "147") (name "/VME_TMS") (class "Default")
      (node (ref "IC40") (pin "R15") (pinfunction "IO_L49P_M1DQ10_1_R15") (pintype "bidirectional"))
    )
    (net (code "148") (name "/VME_TRST") (class "Default")
      (node (ref "IC40") (pin "T13") (pinfunction "IO_L51N_M1DQ13_1_T13") (pintype "bidirectional"))
    )
    (net (code "149") (name "/VME_WRITE_N") (class "Default")
      (node (ref "IC40") (pin "B1") (pinfunction "IO_L50N_M3BA2_3_B1") (pintype "bidirectional"))
    )
    (net (code "150") (name "GND") (class "Default")
      (node (ref "R132") (pin "1") (pinfunction "1_1") (pintype "passive"))
      (node (ref "SW1") (pin "10") (pinfunction "10_10") (pintype "passive"))
      (node (ref "SW1") (pin "11") (pinfunction "11_11") (pintype "passive"))
      (node (ref "SW1") (pin "12") (pinfunction "12_12") (pintype "passive"))
      (node (ref "SW1") (pin "13") (pinfunction "13_13") (pintype "passive"))
      (node (ref "SW1") (pin "14") (pinfunction "14_14") (pintype "passive"))
      (node (ref "SW1") (pin "15") (pinfunction "15_15") (pintype "passive"))
      (node (ref "SW1") (pin "16") (pinfunction "16_16") (pintype "passive"))
      (node (ref "SW1") (pin "9") (pinfunction "9_9") (pintype "passive"))
    )
    (net (code "151") (name "Net-(IC40A-IO_L1P_HSWAPEN_0)") (class "Default")
      (node (ref "IC40") (pin "C4") (pinfunction "IO_L1P_HSWAPEN_0_C4") (pintype "bidirectional"))
      (node (ref "R131") (pin "1") (pinfunction "1_1") (pintype "passive"))
      (node (ref "R132") (pin "2") (pinfunction "2_2") (pintype "passive"))
    )
    (net (code "152") (name "Net-(LD12-C)") (class "Default")
      (node (ref "LD12") (pin "1") (pinfunction "C_1") (pintype "passive"))
      (node (ref "R172") (pin "2") (pinfunction "2_2") (pintype "passive"))
    )
    (net (code "153") (name "Net-(LD18-C)") (class "Default")
      (node (ref "LD18") (pin "1") (pinfunction "C_1") (pintype "passive"))
      (node (ref "R173") (pin "2") (pinfunction "2_2") (pintype "passive"))
    )
    (net (code "154") (name "P3V3") (class "Default")
      (node (ref "LD12") (pin "2") (pinfunction "A_2") (pintype "passive"))
      (node (ref "LD18") (pin "2") (pinfunction "A_2") (pintype "passive"))
      (node (ref "R131") (pin "2") (pinfunction "2_2") (pintype "passive"))
      (node (ref "R133") (pin "2") (pinfunction "2_2") (pintype "passive"))
      (node (ref "R136") (pin "2") (pinfunction "2_2") (pintype "passive"))
      (node (ref "R144") (pin "2") (pinfunction "2_2") (pintype "passive"))
      (node (ref "R149") (pin "2") (pinfunction "2_2") (pintype "passive"))
      (node (ref "R151") (pin "2") (pinfunction "2_2") (pintype "passive"))
      (node (ref "R159") (pin "2") (pinfunction "2_2") (pintype "passive"))
      (node (ref "R160") (pin "2") (pinfunction "2_2") (pintype "passive"))
      (node (ref "R161") (pin "2") (pinfunction "2_2") (pintype "passive"))
    )
    (net (code "155") (name "unconnected-(IC40A-IO_L39N_0-PadA11)") (class "Default")
      (node (ref "IC40") (pin "A11") (pinfunction "IO_L39N_0_A11") (pintype "bidirectional"))
    )
    (net (code "156") (name "unconnected-(IC40A-IO_L40N_0-PadD9)") (class "Default")
      (node (ref "IC40") (pin "D9") (pinfunction "IO_L40N_0_D9") (pintype "bidirectional"))
    )
    (net (code "157") (name "unconnected-(IC40A-IO_L40P_0-PadF9)") (class "Default")
      (node (ref "IC40") (pin "F9") (pinfunction "IO_L40P_0_F9") (pintype "bidirectional"))
    )
    (net (code "158") (name "unconnected-(IC40A-IO_L62N_VREF_0-PadA12)") (class "Default")
      (node (ref "IC40") (pin "A12") (pinfunction "IO_L62N_VREF_0_A12") (pintype "bidirectional"))
    )
    (net (code "159") (name "unconnected-(IC40A-IO_L62P_0-PadB12)") (class "Default")
      (node (ref "IC40") (pin "B12") (pinfunction "IO_L62P_0_B12") (pintype "bidirectional"))
    )
    (net (code "160") (name "unconnected-(IC40A-IO_L63N_SCP6_0-PadA13)") (class "Default")
      (node (ref "IC40") (pin "A13") (pinfunction "IO_L63N_SCP6_0_A13") (pintype "bidirectional"))
    )
    (net (code "161") (name "unconnected-(IC40A-IO_L63P_SCP7_0-PadC13)") (class "Default")
      (node (ref "IC40") (pin "C13") (pinfunction "IO_L63P_SCP7_0_C13") (pintype "bidirectional"))
    )
    (net (code "162") (name "unconnected-(IC40A-IO_L64N_SCP4_0-PadE11)") (class "Default")
      (node (ref "IC40") (pin "E11") (pinfunction "IO_L64N_SCP4_0_E11") (pintype "bidirectional"))
    )
    (net (code "163") (name "unconnected-(IC40A-IO_L64P_SCP5_0-PadF10)") (class "Default")
      (node (ref "IC40") (pin "F10") (pinfunction "IO_L64P_SCP5_0_F10") (pintype "bidirectional"))
    )
    (net (code "164") (name "unconnected-(IC40A-IO_L65N_SCP2_0-PadA14)") (class "Default")
      (node (ref "IC40") (pin "A14") (pinfunction "IO_L65N_SCP2_0_A14") (pintype "bidirectional"))
    )
    (net (code "165") (name "unconnected-(IC40A-IO_L65P_SCP3_0-PadB14)") (class "Default")
      (node (ref "IC40") (pin "B14") (pinfunction "IO_L65P_SCP3_0_B14") (pintype "bidirectional"))
    )
    (net (code "166") (name "unconnected-(IC40A-IO_L66N_SCP0_0-PadD12)") (class "Default")
      (node (ref "IC40") (pin "D12") (pinfunction "IO_L66N_SCP0_0_D12") (pintype "bidirectional"))
    )
    (net (code "167") (name "unconnected-(IC40A-IO_L66P_SCP1_0-PadD11)") (class "Default")
      (node (ref "IC40") (pin "D11") (pinfunction "IO_L66P_SCP1_0_D11") (pintype "bidirectional"))
    )
    (net (code "168") (name "unconnected-(IC40B-IO_L38N_A4_M1CLKN_1-PadH11)") (class "Default")
      (node (ref "IC40") (pin "H11") (pinfunction "IO_L38N_A4_M1CLKN_1_H11") (pintype "bidirectional"))
    )
    (net (code "169") (name "unconnected-(IC40B-IO_L38P_A5_M1CLK_1-PadG12)") (class "Default")
      (node (ref "IC40") (pin "G12") (pinfunction "IO_L38P_A5_M1CLK_1_G12") (pintype "bidirectional"))
    )
    (net (code "170") (name "unconnected-(IC40B-IO_L39N_M1ODT_1-PadH14)") (class "Default")
      (node (ref "IC40") (pin "H14") (pinfunction "IO_L39N_M1ODT_1_H14") (pintype "bidirectional"))
    )
    (net (code "171") (name "unconnected-(IC40B-IO_L39P_M1A3_1-PadH13)") (class "Default")
      (node (ref "IC40") (pin "H13") (pinfunction "IO_L39P_M1A3_1_H13") (pintype "bidirectional"))
    )
    (net (code "172") (name "unconnected-(IC40B-IO_L40N_GCLK10_M1A6_1-PadJ12)") (class "Default")
      (node (ref "IC40") (pin "J12") (pinfunction "IO_L40N_GCLK10_M1A6_1_J12") (pintype "bidirectional"))
    )
    (net (code "173") (name "unconnected-(IC40B-IO_L40P_GCLK11_M1A5_1-PadJ11)") (class "Default")
      (node (ref "IC40") (pin "J11") (pinfunction "IO_L40P_GCLK11_M1A5_1_J11") (pintype "bidirectional"))
    )
    (net (code "174") (name "unconnected-(IC40B-IO_L41N_GCLK8_M1CASN_1-PadK14)") (class "Default")
      (node (ref "IC40") (pin "K14") (pinfunction "IO_L41N_GCLK8_M1CASN_1_K14") (pintype "bidirectional"))
    )
    (net (code "175") (name "unconnected-(IC40B-IO_L41P_GCLK9_IRDY1_M1RASN_1-PadJ13)") (class "Default")
      (node (ref "IC40") (pin "J13") (pinfunction "IO_L41P_GCLK9_IRDY1_M1RASN_1_J13") (pintype "bidirectional"))
    )
    (net (code "176") (name "unconnected-(IC40B-IO_L42N_GCLK6_TRDY1_M1LDM_1-PadK11)") (class "Default")
      (node (ref "IC40") (pin "K11") (pinfunction "IO_L42N_GCLK6_TRDY1_M1LDM_1_K11") (pintype "bidirectional"))
    )
    (net (code "177") (name "unconnected-(IC40B-IO_L42P_GCLK7_M1UDM_1-PadK12)") (class "Default")
      (node (ref "IC40") (pin "K12") (pinfunction "IO_L42P_GCLK7_M1UDM_1_K12") (pintype "bidirectional"))
    )
    (net (code "178") (name "unconnected-(IC40B-IO_L45P_A1_M1LDQS_1-PadN14)") (class "Default")
      (node (ref "IC40") (pin "N14") (pinfunction "IO_L45P_A1_M1LDQS_1_N14") (pintype "bidirectional"))
    )
    (net (code "179") (name "unconnected-(IC40B-IO_L46N_FOE_B_M1DQ3_1-PadM16)") (class "Default")
      (node (ref "IC40") (pin "M16") (pinfunction "IO_L46N_FOE_B_M1DQ3_1_M16") (pintype "bidirectional"))
    )
    (net (code "180") (name "unconnected-(IC40B-IO_L47P_FWE_B_M1DQ0_1-PadL14)") (class "Default")
      (node (ref "IC40") (pin "L14") (pinfunction "IO_L47P_FWE_B_M1DQ0_1_L14") (pintype "bidirectional"))
    )
    (net (code "181") (name "unconnected-(IC40B-IO_L48N_M1DQ9_1-PadP16)") (class "Default")
      (node (ref "IC40") (pin "P16") (pinfunction "IO_L48N_M1DQ9_1_P16") (pintype "bidirectional"))
    )
    (net (code "182") (name "unconnected-(IC40B-IO_L49N_M1DQ11_1-PadR16)") (class "Default")
      (node (ref "IC40") (pin "R16") (pinfunction "IO_L49N_M1DQ11_1_R16") (pintype "bidirectional"))
    )
    (net (code "183") (name "unconnected-(IC40B-IO_L50N_M1UDQSN_1-PadT15)") (class "Default")
      (node (ref "IC40") (pin "T15") (pinfunction "IO_L50N_M1UDQSN_1_T15") (pintype "bidirectional"))
    )
    (net (code "184") (name "unconnected-(IC40B-IO_L53N_VREF_1-PadL13)") (class "Default")
      (node (ref "IC40") (pin "L13") (pinfunction "IO_L53N_VREF_1_L13") (pintype "bidirectional"))
    )
    (net (code "185") (name "unconnected-(IC40B-IO_L53P_1-PadL12)") (class "Default")
      (node (ref "IC40") (pin "L12") (pinfunction "IO_L53P_1_L12") (pintype "bidirectional"))
    )
    (net (code "186") (name "unconnected-(IC40B-IO_L74N_DOUT_BUSY_1-PadM14)") (class "Default")
      (node (ref "IC40") (pin "M14") (pinfunction "IO_L74N_DOUT_BUSY_1_M14") (pintype "bidirectional"))
    )
    (net (code "187") (name "unconnected-(IC40B-IO_L74P_AWAKE_1-PadM13)") (class "Default")
      (node (ref "IC40") (pin "M13") (pinfunction "IO_L74P_AWAKE_1_M13") (pintype "bidirectional"))
    )
    (net (code "188") (name "unconnected-(IC40C-IO_L2N_CMPMOSI_2-PadM11)") (class "Default")
      (node (ref "IC40") (pin "M11") (pinfunction "IO_L2N_CMPMOSI_2_M11") (pintype "bidirectional"))
    )
    (net (code "189") (name "unconnected-(IC40C-IO_L2P_CMPCLK_2-PadM12)") (class "Default")
      (node (ref "IC40") (pin "M12") (pinfunction "IO_L2P_CMPCLK_2_M12") (pintype "bidirectional"))
    )
    (net (code "190") (name "unconnected-(IC40C-IO_L12N_D2_MISO3_2-PadP12)") (class "Default")
      (node (ref "IC40") (pin "P12") (pinfunction "IO_L12N_D2_MISO3_2_P12") (pintype "bidirectional"))
    )
    (net (code "191") (name "unconnected-(IC40C-IO_L12P_D1_MISO2_2-PadN12)") (class "Default")
      (node (ref "IC40") (pin "N12") (pinfunction "IO_L12P_D1_MISO2_2_N12") (pintype "bidirectional"))
    )
    (net (code "192") (name "unconnected-(IC40C-IO_L13N_D10_2-PadP11)") (class "Default")
      (node (ref "IC40") (pin "P11") (pinfunction "IO_L13N_D10_2_P11") (pintype "bidirectional"))
    )
    (net (code "193") (name "unconnected-(IC40D-IO_L43P_GCLK23_M3RASN_3-PadJ6)") (class "Default")
      (node (ref "IC40") (pin "J6") (pinfunction "IO_L43P_GCLK23_M3RASN_3_J6") (pintype "bidirectional"))
    )
    (net (code "194") (name "unconnected-(IC40D-IO_L44P_GCLK21_M3A5_3-PadH4)") (class "Default")
      (node (ref "IC40") (pin "H4") (pinfunction "IO_L44P_GCLK21_M3A5_3_H4") (pintype "bidirectional"))
    )
    (net (code "195") (name "unconnected-(IC40D-IO_L52N_M3A9_3-PadA2)") (class "Default")
      (node (ref "IC40") (pin "A2") (pinfunction "IO_L52N_M3A9_3_A2") (pintype "bidirectional"))
    )
    (net (code "196") (name "unconnected-(IC40D-IO_L53N_M3A12_3-PadF3)") (class "Default")
      (node (ref "IC40") (pin "F3") (pinfunction "IO_L53N_M3A12_3_F3") (pintype "bidirectional"))
    )
  )
)
